# FSG_2019_BSPD_0_2_traversant.net
KiCad netlist of a schematic drawn in EAGLE
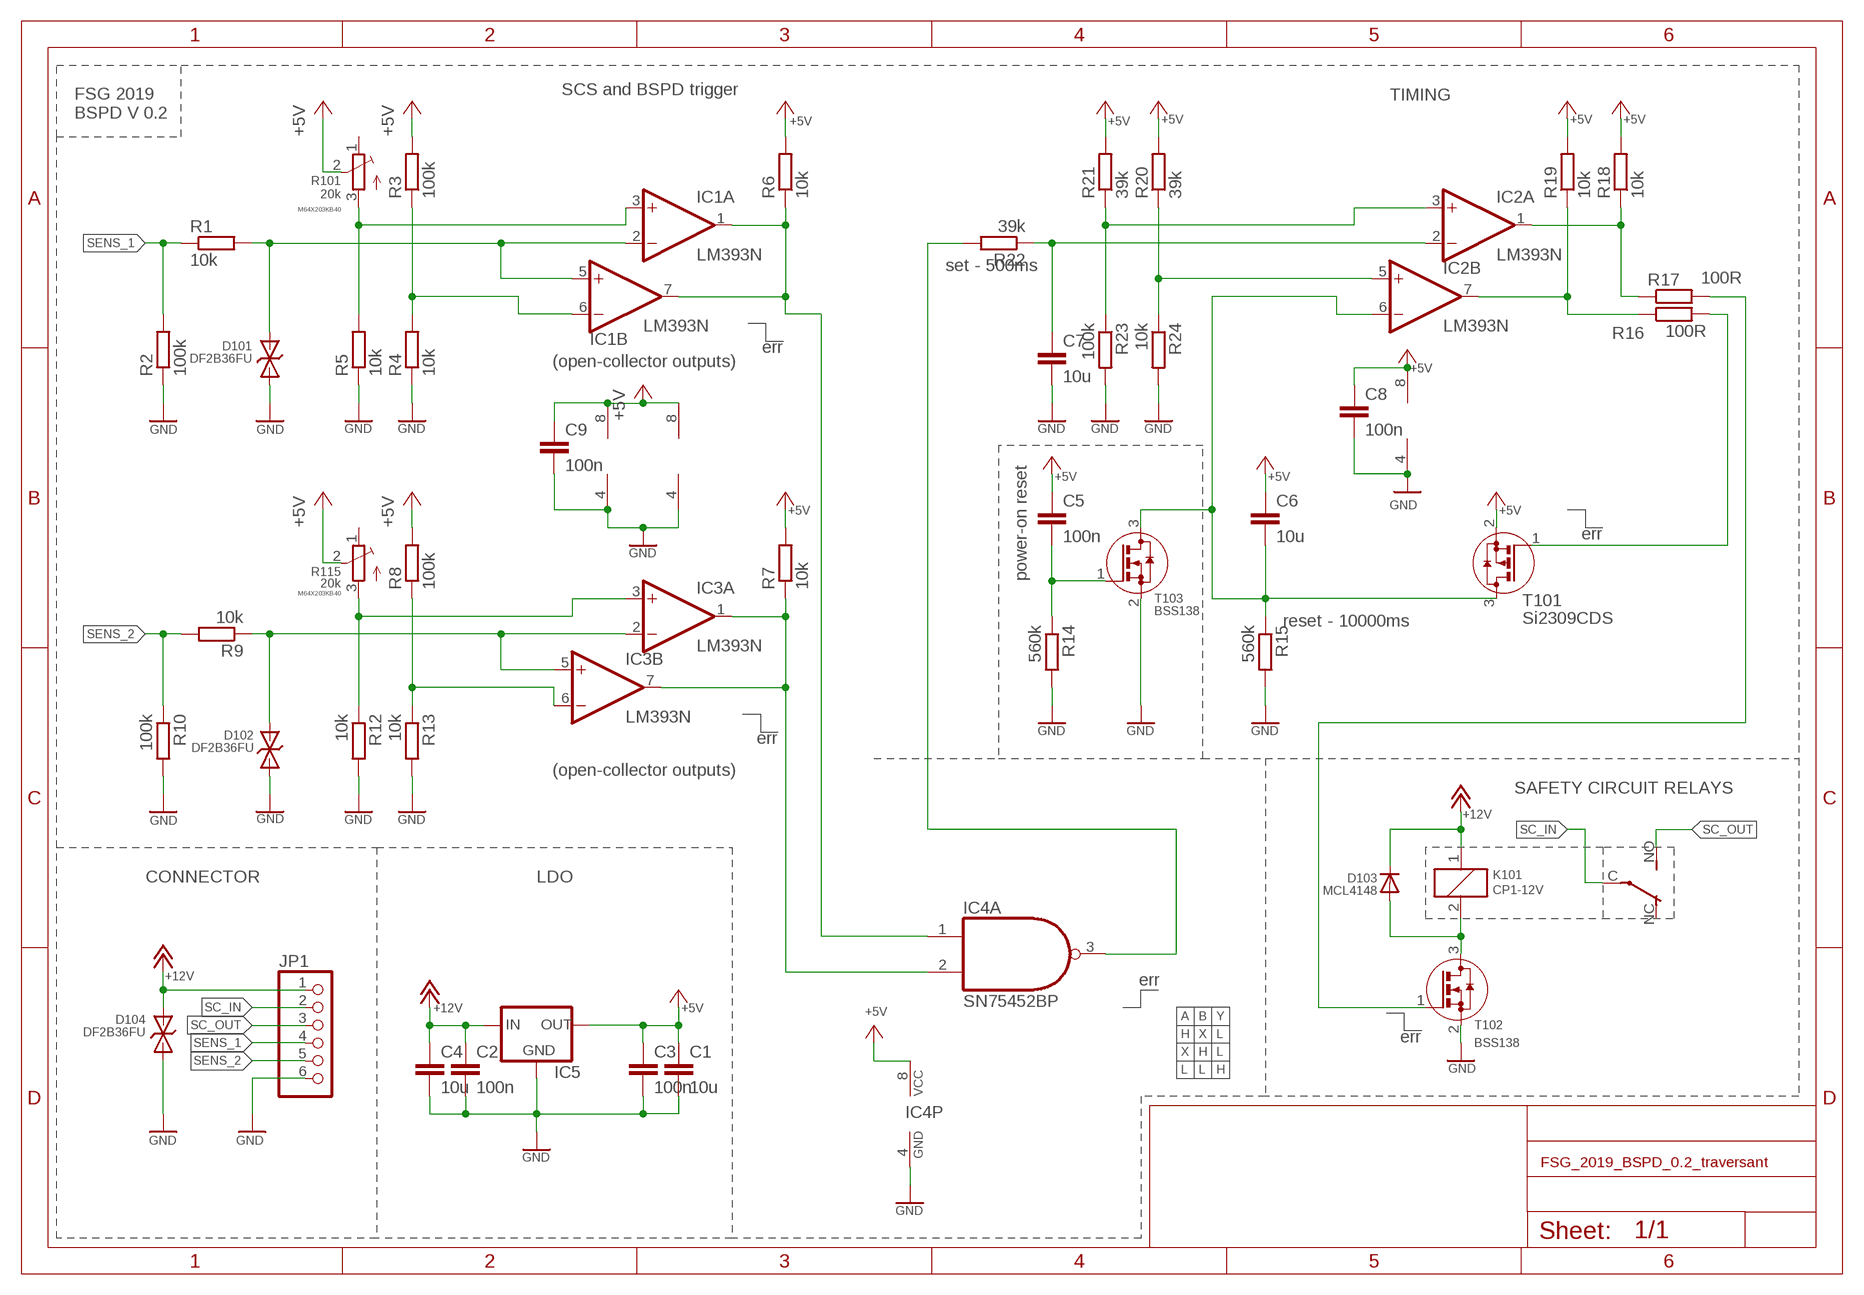
[diagram p0: schematic, sheet 1]

(export (version "E")
  (design (tool "Eeschema 10.0.6"))
  (components
    (comp (ref "C1")
      (value "10u")
      (footprint "eagle-import:C075-052X106")
      (libsource (lib "eagle-import") (part "C-EU075-052X106"))
    )
    (comp (ref "C2")
      (value "100n")
      (footprint "eagle-import:C025-024X044")
      (libsource (lib "eagle-import") (part "C-EU025-024X044"))
    )
    (comp (ref "C3")
      (value "100n")
      (footprint "eagle-import:C025-024X044")
      (libsource (lib "eagle-import") (part "C-EU025-024X044"))
    )
    (comp (ref "C4")
      (value "10u")
      (footprint "eagle-import:C075-052X106")
      (libsource (lib "eagle-import") (part "C-EU075-052X106"))
    )
    (comp (ref "C5")
      (value "100n")
      (footprint "eagle-import:C025-024X044")
      (libsource (lib "eagle-import") (part "C-EU025-024X044"))
    )
    (comp (ref "C6")
      (value "10u")
      (footprint "eagle-import:C075-052X106")
      (libsource (lib "eagle-import") (part "C-EU075-052X106"))
    )
    (comp (ref "C7")
      (value "10u")
      (footprint "eagle-import:C075-052X106")
      (libsource (lib "eagle-import") (part "C-EU075-052X106"))
    )
    (comp (ref "C8")
      (value "100n")
      (footprint "eagle-import:C025-024X044")
      (libsource (lib "eagle-import") (part "C-EU025-024X044"))
    )
    (comp (ref "C9")
      (value "100n")
      (footprint "eagle-import:C025-024X044")
      (libsource (lib "eagle-import") (part "C-EU025-024X044"))
    )
    (comp (ref "D101")
      (value "DF2B36FU")
      (footprint "eagle-import:SOD323")
      (libsource (lib "eagle-import") (part "DF2B36FU"))
    )
    (comp (ref "D102")
      (value "DF2B36FU")
      (footprint "eagle-import:SOD323")
      (libsource (lib "eagle-import") (part "DF2B36FU"))
    )
    (comp (ref "D103")
      (value "MCL4148")
      (footprint "eagle-import:MICROMELF")
      (libsource (lib "eagle-import") (part "D.MCL4148"))
    )
    (comp (ref "D104")
      (value "DF2B36FU")
      (footprint "eagle-import:SOD323")
      (libsource (lib "eagle-import") (part "DF2B36FU"))
    )
    (comp (ref "IC1")
      (value "LM393N")
      (footprint "eagle-import:DIL08")
      (libsource (lib "eagle-import") (part "LM393N"))
    )
    (comp (ref "IC2")
      (value "LM393N")
      (footprint "eagle-import:DIL08")
      (libsource (lib "eagle-import") (part "LM393N"))
    )
    (comp (ref "IC3")
      (value "LM393N")
      (footprint "eagle-import:DIL08")
      (libsource (lib "eagle-import") (part "LM393N"))
    )
    (comp (ref "IC4")
      (value "SN75452BP")
      (footprint "eagle-import:DIL08")
      (libsource (lib "eagle-import") (part "SN75452BP"))
    )
    (comp (ref "IC5")
      (value "LM1117V")
      (footprint "eagle-import:78XXS")
      (libsource (lib "eagle-import") (part "LM1117V"))
    )
    (comp (ref "JP1")
      (value "PINHD-1X6")
      (footprint "eagle-import:1X06")
      (libsource (lib "eagle-import") (part "PINHD-1X6"))
    )
    (comp (ref "K101")
      (value "CP1-12V")
      (footprint "eagle-import:CP1")
      (fields (field (name "MF") "AROMAT/ MATSUSHITA"))
      (libsource (lib "eagle-import") (part "CP1?-12V"))
    )
    (comp (ref "R1")
      (value "10k")
      (footprint "eagle-import:0204_7")
      (libsource (lib "eagle-import") (part "R-EU_0204/7"))
    )
    (comp (ref "R2")
      (value "100k")
      (footprint "eagle-import:0204_7")
      (libsource (lib "eagle-import") (part "R-EU_0204/7"))
    )
    (comp (ref "R3")
      (value "100k")
      (footprint "eagle-import:0204_7")
      (libsource (lib "eagle-import") (part "R-EU_0204/7"))
    )
    (comp (ref "R4")
      (value "10k")
      (footprint "eagle-import:0204_7")
      (libsource (lib "eagle-import") (part "R-EU_0204/7"))
    )
    (comp (ref "R5")
      (value "10k")
      (footprint "eagle-import:0204_7")
      (libsource (lib "eagle-import") (part "R-EU_0204/7"))
    )
    (comp (ref "R6")
      (value "10k")
      (footprint "eagle-import:0204_7")
      (libsource (lib "eagle-import") (part "R-EU_0204/7"))
    )
    (comp (ref "R7")
      (value "10k")
      (footprint "eagle-import:0204_7")
      (libsource (lib "eagle-import") (part "R-EU_0204/7"))
    )
    (comp (ref "R8")
      (value "100k")
      (footprint "eagle-import:0204_7")
      (libsource (lib "eagle-import") (part "R-EU_0204/7"))
    )
    (comp (ref "R9")
      (value "10k")
      (footprint "eagle-import:0204_7")
      (libsource (lib "eagle-import") (part "R-EU_0204/7"))
    )
    (comp (ref "R10")
      (value "100k")
      (footprint "eagle-import:0204_7")
      (libsource (lib "eagle-import") (part "R-EU_0204/7"))
    )
    (comp (ref "R12")
      (value "10k")
      (footprint "eagle-import:0204_7")
      (libsource (lib "eagle-import") (part "R-EU_0204/7"))
    )
    (comp (ref "R13")
      (value "10k")
      (footprint "eagle-import:0204_7")
      (libsource (lib "eagle-import") (part "R-EU_0204/7"))
    )
    (comp (ref "R14")
      (value "560k")
      (footprint "eagle-import:0204_7")
      (libsource (lib "eagle-import") (part "R-EU_0204/7"))
    )
    (comp (ref "R15")
      (value "560k")
      (footprint "eagle-import:0204_7")
      (libsource (lib "eagle-import") (part "R-EU_0204/7"))
    )
    (comp (ref "R16")
      (value "100R")
      (footprint "eagle-import:0204_7")
      (libsource (lib "eagle-import") (part "R-EU_0204/7"))
    )
    (comp (ref "R17")
      (value "100R")
      (footprint "eagle-import:0204_7")
      (libsource (lib "eagle-import") (part "R-EU_0204/7"))
    )
    (comp (ref "R18")
      (value "10k")
      (footprint "eagle-import:0204_7")
      (libsource (lib "eagle-import") (part "R-EU_0204/7"))
    )
    (comp (ref "R19")
      (value "10k")
      (footprint "eagle-import:0204_7")
      (libsource (lib "eagle-import") (part "R-EU_0204/7"))
    )
    (comp (ref "R20")
      (value "39k")
      (footprint "eagle-import:0204_7")
      (libsource (lib "eagle-import") (part "R-EU_0204/7"))
    )
    (comp (ref "R21")
      (value "39k")
      (footprint "eagle-import:0204_7")
      (libsource (lib "eagle-import") (part "R-EU_0204/7"))
    )
    (comp (ref "R22")
      (value "39k")
      (footprint "eagle-import:0204_7")
      (libsource (lib "eagle-import") (part "R-EU_0204/7"))
    )
    (comp (ref "R23")
      (value "100k")
      (footprint "eagle-import:0204_7")
      (libsource (lib "eagle-import") (part "R-EU_0204/7"))
    )
    (comp (ref "R24")
      (value "10k")
      (footprint "eagle-import:0204_7")
      (libsource (lib "eagle-import") (part "R-EU_0204/7"))
    )
    (comp (ref "R101")
      (value "20k")
      (footprint "eagle-import:M64X201KB40")
      (libsource (lib "eagle-import") (part "POTI.M64X201KB40"))
    )
    (comp (ref "R115")
      (value "20k")
      (footprint "eagle-import:M64X201KB40")
      (libsource (lib "eagle-import") (part "POTI.M64X201KB40"))
    )
    (comp (ref "T101")
      (value "Si2309CDS")
      (footprint "eagle-import:SOT-23")
      (libsource (lib "eagle-import") (part "P-MOSFET.SOT23"))
    )
    (comp (ref "T102")
      (value "BSS138")
      (footprint "eagle-import:SOT-23")
      (libsource (lib "eagle-import") (part "N-MOSFET.SOT23"))
    )
    (comp (ref "T103")
      (value "BSS138")
      (footprint "eagle-import:SOT-23")
      (libsource (lib "eagle-import") (part "N-MOSFET.SOT23"))
    )
  )
  (nets
    (net (code "1") (name "+5V") (class "Default")
      (node (ref "C1") (pin "1") (pinfunction "1_1") (pintype "passive"))
      (node (ref "C3") (pin "1") (pinfunction "1_1") (pintype "passive"))
      (node (ref "C5") (pin "1") (pinfunction "1_1") (pintype "passive"))
      (node (ref "C6") (pin "1") (pinfunction "1_1") (pintype "passive"))
      (node (ref "C8") (pin "1") (pinfunction "1_1") (pintype "passive"))
      (node (ref "C9") (pin "1") (pinfunction "1_1") (pintype "passive"))
      (node (ref "IC1") (pin "8") (pinfunction "V+_8") (pintype "power_in"))
      (node (ref "IC2") (pin "8") (pinfunction "V+_8") (pintype "power_in"))
      (node (ref "IC3") (pin "8") (pinfunction "V+_8") (pintype "power_in"))
      (node (ref "IC4") (pin "8") (pinfunction "VCC_8") (pintype "power_in"))
      (node (ref "IC5") (pin "OUT") (pinfunction "OUT_OUT") (pintype "passive"))
      (node (ref "R101") (pin "2") (pinfunction "M_2") (pintype "passive"))
      (node (ref "R115") (pin "2") (pinfunction "M_2") (pintype "passive"))
      (node (ref "R18") (pin "2") (pinfunction "2_2") (pintype "passive"))
      (node (ref "R19") (pin "2") (pinfunction "2_2") (pintype "passive"))
      (node (ref "R20") (pin "2") (pinfunction "2_2") (pintype "passive"))
      (node (ref "R21") (pin "2") (pinfunction "2_2") (pintype "passive"))
      (node (ref "R3") (pin "2") (pinfunction "2_2") (pintype "passive"))
      (node (ref "R6") (pin "2") (pinfunction "2_2") (pintype "passive"))
      (node (ref "R7") (pin "2") (pinfunction "2_2") (pintype "passive"))
      (node (ref "R8") (pin "2") (pinfunction "2_2") (pintype "passive"))
      (node (ref "T101") (pin "2") (pinfunction "S_2") (pintype "passive"))
    )
    (net (code "2") (name "+12V") (class "Default")
      (node (ref "C2") (pin "1") (pinfunction "1_1") (pintype "passive"))
      (node (ref "C4") (pin "1") (pinfunction "1_1") (pintype "passive"))
      (node (ref "D103") (pin "C") (pinfunction "C_C") (pintype "passive"))
      (node (ref "D104") (pin "2") (pinfunction "C_2") (pintype "passive"))
      (node (ref "IC5") (pin "IN") (pinfunction "IN_IN") (pintype "input"))
      (node (ref "JP1") (pin "1") (pinfunction "1_1") (pintype "passive"))
      (node (ref "K101") (pin "1") (pinfunction "1_1") (pintype "passive"))
    )
    (net (code "3") (name "GND") (class "Default")
      (node (ref "C1") (pin "2") (pinfunction "2_2") (pintype "passive"))
      (node (ref "C2") (pin "2") (pinfunction "2_2") (pintype "passive"))
      (node (ref "C3") (pin "2") (pinfunction "2_2") (pintype "passive"))
      (node (ref "C4") (pin "2") (pinfunction "2_2") (pintype "passive"))
      (node (ref "C7") (pin "2") (pinfunction "2_2") (pintype "passive"))
      (node (ref "C8") (pin "2") (pinfunction "2_2") (pintype "passive"))
      (node (ref "C9") (pin "2") (pinfunction "2_2") (pintype "passive"))
      (node (ref "D101") (pin "1") (pinfunction "A_1") (pintype "passive"))
      (node (ref "D102") (pin "1") (pinfunction "A_1") (pintype "passive"))
      (node (ref "D104") (pin "1") (pinfunction "A_1") (pintype "passive"))
      (node (ref "IC1") (pin "4") (pinfunction "V-_4") (pintype "power_in"))
      (node (ref "IC2") (pin "4") (pinfunction "V-_4") (pintype "power_in"))
      (node (ref "IC3") (pin "4") (pinfunction "V-_4") (pintype "power_in"))
      (node (ref "IC4") (pin "4") (pinfunction "GND_4") (pintype "power_in"))
      (node (ref "IC5") (pin "GND") (pinfunction "GND_GND") (pintype "input"))
      (node (ref "JP1") (pin "6") (pinfunction "6_6") (pintype "passive"))
      (node (ref "R10") (pin "2") (pinfunction "2_2") (pintype "passive"))
      (node (ref "R12") (pin "2") (pinfunction "2_2") (pintype "passive"))
      (node (ref "R13") (pin "2") (pinfunction "2_2") (pintype "passive"))
      (node (ref "R14") (pin "2") (pinfunction "2_2") (pintype "passive"))
      (node (ref "R15") (pin "2") (pinfunction "2_2") (pintype "passive"))
      (node (ref "R2") (pin "1") (pinfunction "1_1") (pintype "passive"))
      (node (ref "R23") (pin "2") (pinfunction "2_2") (pintype "passive"))
      (node (ref "R24") (pin "2") (pinfunction "2_2") (pintype "passive"))
      (node (ref "R4") (pin "1") (pinfunction "1_1") (pintype "passive"))
      (node (ref "R5") (pin "1") (pinfunction "1_1") (pintype "passive"))
      (node (ref "T102") (pin "2") (pinfunction "S_2") (pintype "passive"))
      (node (ref "T103") (pin "2") (pinfunction "S_2") (pintype "passive"))
    )
    (net (code "4") (name "Net-(D101-C)") (class "Default")
      (node (ref "D101") (pin "2") (pinfunction "C_2") (pintype "passive"))
      (node (ref "IC1") (pin "2") (pinfunction "-IN_2") (pintype "input"))
      (node (ref "IC1") (pin "5") (pinfunction "+IN_5") (pintype "input"))
      (node (ref "R1") (pin "2") (pinfunction "2_2") (pintype "passive"))
    )
    (net (code "5") (name "Net-(D102-C)") (class "Default")
      (node (ref "D102") (pin "2") (pinfunction "C_2") (pintype "passive"))
      (node (ref "IC3") (pin "2") (pinfunction "-IN_2") (pintype "input"))
      (node (ref "IC3") (pin "5") (pinfunction "+IN_5") (pintype "input"))
      (node (ref "R9") (pin "1") (pinfunction "1_1") (pintype "passive"))
    )
    (net (code "6") (name "Net-(IC1A-+IN)") (class "Default")
      (node (ref "IC1") (pin "3") (pinfunction "+IN_3") (pintype "input"))
      (node (ref "R101") (pin "3") (pinfunction "A_3") (pintype "passive"))
      (node (ref "R5") (pin "2") (pinfunction "2_2") (pintype "passive"))
    )
    (net (code "7") (name "Net-(IC1A-OUT)") (class "Default")
      (node (ref "IC1") (pin "1") (pinfunction "OUT_1") (pintype "output"))
      (node (ref "IC1") (pin "7") (pinfunction "OUT_7") (pintype "output"))
      (node (ref "IC4") (pin "1") (pinfunction "I0_1") (pintype "input"))
      (node (ref "R6") (pin "1") (pinfunction "1_1") (pintype "passive"))
    )
    (net (code "8") (name "Net-(IC1B--IN)") (class "Default")
      (node (ref "IC1") (pin "6") (pinfunction "-IN_6") (pintype "input"))
      (node (ref "R3") (pin "1") (pinfunction "1_1") (pintype "passive"))
      (node (ref "R4") (pin "2") (pinfunction "2_2") (pintype "passive"))
    )
    (net (code "9") (name "Net-(IC2A-+IN)") (class "Default")
      (node (ref "IC2") (pin "3") (pinfunction "+IN_3") (pintype "input"))
      (node (ref "R21") (pin "1") (pinfunction "1_1") (pintype "passive"))
      (node (ref "R23") (pin "1") (pinfunction "1_1") (pintype "passive"))
    )
    (net (code "10") (name "Net-(IC2A--IN)") (class "Default")
      (node (ref "C7") (pin "1") (pinfunction "1_1") (pintype "passive"))
      (node (ref "IC2") (pin "2") (pinfunction "-IN_2") (pintype "input"))
      (node (ref "R22") (pin "1") (pinfunction "1_1") (pintype "passive"))
    )
    (net (code "11") (name "Net-(IC2A-OUT)") (class "Default")
      (node (ref "IC2") (pin "1") (pinfunction "OUT_1") (pintype "output"))
      (node (ref "R17") (pin "1") (pinfunction "1_1") (pintype "passive"))
      (node (ref "R18") (pin "1") (pinfunction "1_1") (pintype "passive"))
    )
    (net (code "12") (name "Net-(IC2B-+IN)") (class "Default")
      (node (ref "IC2") (pin "5") (pinfunction "+IN_5") (pintype "input"))
      (node (ref "R20") (pin "1") (pinfunction "1_1") (pintype "passive"))
      (node (ref "R24") (pin "1") (pinfunction "1_1") (pintype "passive"))
    )
    (net (code "13") (name "Net-(IC2B--IN)") (class "Default")
      (node (ref "C6") (pin "2") (pinfunction "2_2") (pintype "passive"))
      (node (ref "IC2") (pin "6") (pinfunction "-IN_6") (pintype "input"))
      (node (ref "R15") (pin "1") (pinfunction "1_1") (pintype "passive"))
      (node (ref "T101") (pin "3") (pinfunction "D_3") (pintype "passive"))
      (node (ref "T103") (pin "3") (pinfunction "D_3") (pintype "passive"))
    )
    (net (code "14") (name "Net-(IC2B-OUT)") (class "Default")
      (node (ref "IC2") (pin "7") (pinfunction "OUT_7") (pintype "output"))
      (node (ref "R16") (pin "1") (pinfunction "1_1") (pintype "passive"))
      (node (ref "R19") (pin "1") (pinfunction "1_1") (pintype "passive"))
    )
    (net (code "15") (name "Net-(IC3A-+IN)") (class "Default")
      (node (ref "IC3") (pin "3") (pinfunction "+IN_3") (pintype "input"))
      (node (ref "R115") (pin "3") (pinfunction "A_3") (pintype "passive"))
      (node (ref "R12") (pin "1") (pinfunction "1_1") (pintype "passive"))
    )
    (net (code "16") (name "Net-(IC3A-OUT)") (class "Default")
      (node (ref "IC3") (pin "1") (pinfunction "OUT_1") (pintype "output"))
      (node (ref "IC3") (pin "7") (pinfunction "OUT_7") (pintype "output"))
      (node (ref "IC4") (pin "2") (pinfunction "I1_2") (pintype "input"))
      (node (ref "R7") (pin "1") (pinfunction "1_1") (pintype "passive"))
    )
    (net (code "17") (name "Net-(IC3B--IN)") (class "Default")
      (node (ref "IC3") (pin "6") (pinfunction "-IN_6") (pintype "input"))
      (node (ref "R13") (pin "1") (pinfunction "1_1") (pintype "passive"))
      (node (ref "R8") (pin "1") (pinfunction "1_1") (pintype "passive"))
    )
    (net (code "18") (name "Net-(IC4A-O)") (class "Default")
      (node (ref "IC4") (pin "3") (pinfunction "O_3") (pintype "output"))
      (node (ref "R22") (pin "2") (pinfunction "2_2") (pintype "passive"))
    )
    (net (code "19") (name "Net-(T101-G)") (class "Default")
      (node (ref "R16") (pin "2") (pinfunction "2_2") (pintype "passive"))
      (node (ref "T101") (pin "1") (pinfunction "G_1") (pintype "passive"))
    )
    (net (code "20") (name "Net-(T102-D)") (class "Default")
      (node (ref "D103") (pin "A") (pinfunction "A_A") (pintype "passive"))
      (node (ref "K101") (pin "2") (pinfunction "2_2") (pintype "passive"))
      (node (ref "T102") (pin "3") (pinfunction "D_3") (pintype "passive"))
    )
    (net (code "21") (name "Net-(T102-G)") (class "Default")
      (node (ref "R17") (pin "2") (pinfunction "2_2") (pintype "passive"))
      (node (ref "T102") (pin "1") (pinfunction "G_1") (pintype "passive"))
    )
    (net (code "22") (name "Net-(T103-G)") (class "Default")
      (node (ref "C5") (pin "2") (pinfunction "2_2") (pintype "passive"))
      (node (ref "R14") (pin "1") (pinfunction "1_1") (pintype "passive"))
      (node (ref "T103") (pin "1") (pinfunction "G_1") (pintype "passive"))
    )
    (net (code "23") (name "SC_IN") (class "Default")
      (node (ref "JP1") (pin "2") (pinfunction "2_2") (pintype "passive"))
      (node (ref "K101") (pin "C") (pinfunction "P_C") (pintype "passive"))
    )
    (net (code "24") (name "SC_OUT") (class "Default")
      (node (ref "JP1") (pin "3") (pinfunction "3_3") (pintype "passive"))
      (node (ref "K101") (pin "NO") (pinfunction "S_NO") (pintype "passive"))
    )
    (net (code "25") (name "SENS_1") (class "Default")
      (node (ref "JP1") (pin "4") (pinfunction "4_4") (pintype "passive"))
      (node (ref "R1") (pin "1") (pinfunction "1_1") (pintype "passive"))
      (node (ref "R2") (pin "2") (pinfunction "2_2") (pintype "passive"))
    )
    (net (code "26") (name "SENS_2") (class "Default")
      (node (ref "JP1") (pin "5") (pinfunction "5_5") (pintype "passive"))
      (node (ref "R10") (pin "1") (pinfunction "1_1") (pintype "passive"))
      (node (ref "R9") (pin "2") (pinfunction "2_2") (pintype "passive"))
    )
    (net (code "27") (name "unconnected-(K101B-O-PadNC)") (class "Default")
      (node (ref "K101") (pin "NC") (pinfunction "O_NC") (pintype "passive"))
    )
    (net (code "28") (name "unconnected-(R101-E-Pad1)") (class "Default")
      (node (ref "R101") (pin "1") (pinfunction "E_1") (pintype "passive"))
    )
    (net (code "29") (name "unconnected-(R115-E-Pad1)") (class "Default")
      (node (ref "R115") (pin "1") (pinfunction "E_1") (pintype "passive"))
    )
  )
)
